# gameConsole.net
KiCad netlist of a schematic drawn in Altium Designer
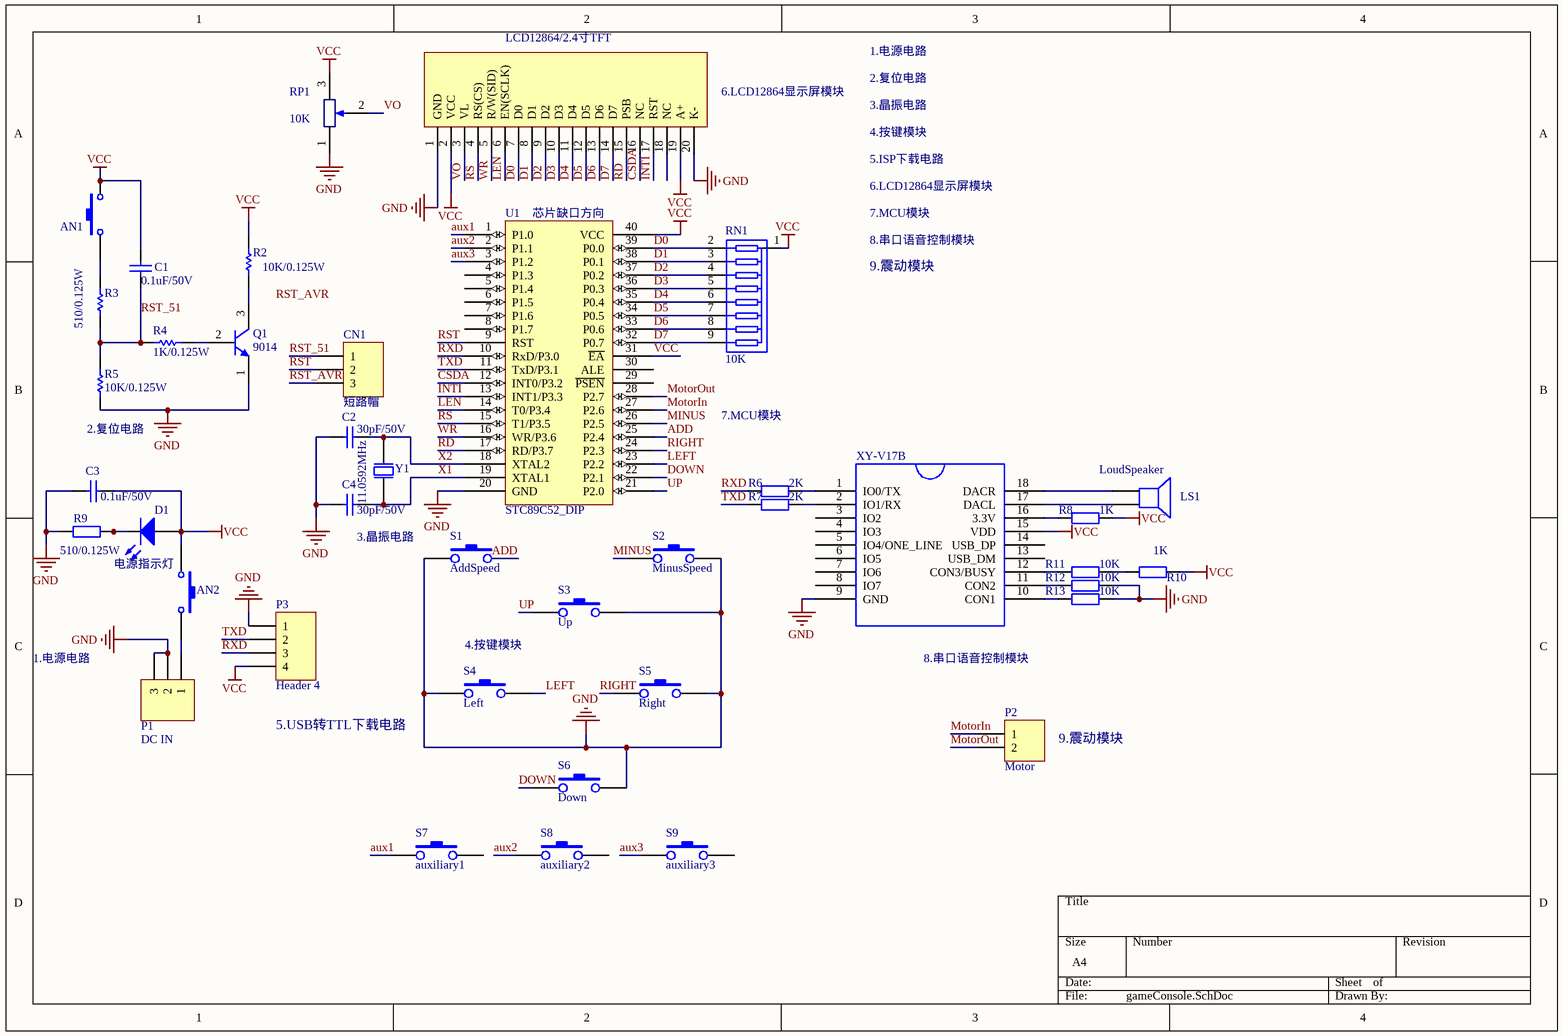
[diagram p0: gameConsole.SchDoc]

(export (version "E")
  (design (tool "Eeschema 10.0.6"))
  (components
    (comp (ref "AN1")
      (value "Button")
      (footprint "BUTTON_6*6")
      (fields (field (name "PUBLISHER") "Altium Limited"))
      (libsource (lib "03-EButterflyIntegratedLibrary") (part "Button"))
    )
    (comp (ref "AN2")
      (value "微动开关")
      (footprint "sw_8.5mm")
      (description "Button")
      (fields (field (name "PUBLISHER") "Altium Limited"))
      (libsource (lib "03-EButterflyIntegratedLibrary") (part "Button"))
    )
    (comp (ref "C1")
      (value "0.1uF/50V")
      (footprint "Cap")
      (description "Capacitor")
      (fields (field (name "PUBLISHER") "Altium Limited"))
      (libsource (lib "Miscellaneous Devices") (part "Cap"))
    )
    (comp (ref "C2")
      (value "30pF/50V")
      (footprint "Cap")
      (description "Capacitor")
      (fields (field (name "Comment") "Cap") (field (name "PUBLISHER") "Altium Limited"))
      (libsource (lib "Miscellaneous Devices") (part "Cap"))
    )
    (comp (ref "C3")
      (value "0.1uF/50V")
      (footprint "Cap")
      (description "Capacitor")
      (fields (field (name "PUBLISHER") "Altium Limited"))
      (libsource (lib "Miscellaneous Devices") (part "Cap"))
    )
    (comp (ref "C4")
      (value "30pF/50V")
      (footprint "Cap")
      (description "Capacitor")
      (fields (field (name "PUBLISHER") "Altium Limited"))
      (libsource (lib "Miscellaneous Devices") (part "Cap"))
    )
    (comp (ref "CN1")
      (value "短路帽")
      (footprint "SIP-3")
      (description "Header, 3-Pin")
      (fields (field (name "PUBLISHER") "Altium Limited"))
      (libsource (lib "01 Connect_IntegratedLibrary") (part "Header 3"))
    )
    (comp (ref "D1")
      (value "电源指示灯")
      (footprint "LED-1")
      (description "Typical RED GaAs LED")
      (fields (field (name "PUBLISHER") "Altium Limited"))
      (libsource (lib "Miscellaneous Devices") (part "LED1"))
    )
    (comp (ref "LCD1")
      (value "LCD12864/2.4寸TFT")
      (footprint "HDR1X20")
      (description "LCD12864 带字库")
      (libsource (lib "02 Miscellaneous_Devices_ZSF_Library") (part "LCD12864_1"))
    )
    (comp (ref "LS1")
      (value "LoudSpeaker")
      (footprint "扬声器")
      (description "Loudspeaker")
      (fields (field (name "PUBLISHER") "Altium Limited"))
      (libsource (lib "Miscellaneous Devices") (part "Speaker"))
    )
    (comp (ref "P1")
      (value "DC IN")
      (footprint "DC_IN")
      (description "Header, 3-Pin")
      (fields (field (name "PUBLISHER") "Altium Limited"))
      (libsource (lib "Miscellaneous Connectors") (part "Header 3"))
    )
    (comp (ref "P2")
      (value "Motor")
      (footprint "震动马达")
      (description "Header, 2-Pin")
      (fields (field (name "PUBLISHER") "Altium Limited"))
      (libsource (lib "Miscellaneous Connectors") (part "Header 2"))
    )
    (comp (ref "P3")
      (value "Header 4")
      (footprint "USB转TTL")
      (description "Header, 4-Pin")
      (fields (field (name "PUBLISHER") "Altium Limited"))
      (libsource (lib "01 Connect_IntegratedLibrary") (part "Header 4"))
    )
    (comp (ref "Q1")
      (value "9014")
      (footprint "TO-92-3L")
      (description "NPN型小功率三极管")
      (libsource (lib "02 Miscellaneous_Devices_ZSF_Library") (part "9014_TO-92"))
    )
    (comp (ref "R2")
      (value "10K/0.125W")
      (footprint "AXIAL-0.4")
      (description "Resistor")
      (fields (field (name "Comment") "Res1") (field (name "PUBLISHER") "Altium Limited"))
      (libsource (lib "Miscellaneous Devices") (part "Res1"))
    )
    (comp (ref "R3")
      (value "510/0.125W")
      (footprint "AXIAL-0.4")
      (description "Resistor")
      (fields (field (name "PUBLISHER") "Altium Limited"))
      (libsource (lib "Miscellaneous Devices") (part "Res1"))
    )
    (comp (ref "R4")
      (value "1K/0.125W")
      (footprint "AXIAL-0.4")
      (description "Resistor")
      (fields (field (name "PUBLISHER") "Altium Limited"))
      (libsource (lib "Miscellaneous Devices") (part "Res1"))
    )
    (comp (ref "R5")
      (value "10K/0.125W")
      (footprint "AXIAL-0.4")
      (description "Resistor")
      (fields (field (name "PUBLISHER") "Altium Limited"))
      (libsource (lib "Miscellaneous Devices") (part "Res1"))
    )
    (comp (ref "R6")
      (value "2K")
      (footprint "AXIAL-0.4")
      (description "Resistor")
      (fields (field (name "PUBLISHER") "Altium Limited"))
      (libsource (lib "Miscellaneous Devices") (part "Res2"))
    )
    (comp (ref "R7")
      (value "2K")
      (footprint "AXIAL-0.4")
      (description "Resistor")
      (fields (field (name "PUBLISHER") "Altium Limited"))
      (libsource (lib "Miscellaneous Devices") (part "Res2"))
    )
    (comp (ref "R8")
      (value "1K")
      (footprint "AXIAL-0.4")
      (description "Resistor")
      (fields (field (name "Comment") "Res2") (field (name "PUBLISHER") "Altium Limited"))
      (libsource (lib "Miscellaneous Devices") (part "Res2"))
    )
    (comp (ref "R9")
      (value "510/0.125W")
      (footprint "AXIAL-0.4")
      (description "Resistor")
      (fields (field (name "PUBLISHER") "Altium Limited"))
      (libsource (lib "Miscellaneous Devices") (part "Res2"))
    )
    (comp (ref "R10")
      (value "1K")
      (footprint "AXIAL-0.4")
      (description "Resistor")
      (fields (field (name "PUBLISHER") "Altium Limited"))
      (libsource (lib "Miscellaneous Devices") (part "Res2"))
    )
    (comp (ref "R11")
      (value "10K")
      (footprint "AXIAL-0.4")
      (description "Resistor")
      (fields (field (name "PUBLISHER") "Altium Limited"))
      (libsource (lib "Miscellaneous Devices") (part "Res2"))
    )
    (comp (ref "R12")
      (value "10K")
      (footprint "AXIAL-0.4")
      (description "Resistor")
      (fields (field (name "PUBLISHER") "Altium Limited"))
      (libsource (lib "Miscellaneous Devices") (part "Res2"))
    )
    (comp (ref "R13")
      (value "10K")
      (footprint "AXIAL-0.4")
      (description "Resistor")
      (fields (field (name "PUBLISHER") "Altium Limited"))
      (libsource (lib "Miscellaneous Devices") (part "Res2"))
    )
    (comp (ref "RN1")
      (value "10K")
      (footprint "RES-PACK-DIP9")
      (description "10K排阻")
      (fields (field (name "Comment") "Res Pack Single"))
      (libsource (lib "03-EButterflyIntegratedLibrary") (part "Res Pack Single"))
    )
    (comp (ref "RP1")
      (value "10K")
      (footprint "RP-3362")
      (description "WH148单联电位器 3脚 柄长15mm")
      (libsource (lib "02 Miscellaneous_Devices_ZSF_Library") (part "RP_WH148_Signal"))
    )
    (comp (ref "S1") (value "AddSpeed") (footprint "BUTTON_6*6") (libsource (lib "开关") (part "微动开关")))
    (comp (ref "S2") (value "MinusSpeed") (footprint "BUTTON_6*6") (libsource (lib "开关") (part "微动开关")))
    (comp (ref "S3") (value "Up") (footprint "BUTTON_6*6") (libsource (lib "开关") (part "微动开关")))
    (comp (ref "S4") (value "Left") (footprint "BUTTON_6*6") (libsource (lib "开关") (part "微动开关")))
    (comp (ref "S5") (value "Right") (footprint "BUTTON_6*6") (libsource (lib "开关") (part "微动开关")))
    (comp (ref "S6") (value "Down") (footprint "BUTTON_6*6") (libsource (lib "开关") (part "微动开关")))
    (comp (ref "S7") (value "auxiliary1") (footprint "BUTTON_6*6") (libsource (lib "开关") (part "微动开关")))
    (comp (ref "S8") (value "auxiliary2") (footprint "BUTTON_6*6") (libsource (lib "开关") (part "微动开关")))
    (comp (ref "S9") (value "auxiliary3") (footprint "BUTTON_6*6") (libsource (lib "开关") (part "微动开关")))
    (comp (ref "U1")
      (value "STC89C52_DIP")
      (footprint "DIP-40")
      (libsource (lib "02 Miscellaneous_Devices_ZSF_Library") (part "STC89C52_DIP"))
    )
    (comp (ref "XY-V17B") (value "XY-V17B") (footprint "SV1700A") (libsource (lib "Schlib1") (part "MODULE")))
    (comp (ref "Y1")
      (value "XTAL")
      (footprint "XTAL-49/U_N")
      (description "Crystal Oscillator")
      (fields (field (name "FREQUENCY") "11.0592MHz") (field (name "PUBLISHER") "Altium Limited"))
      (libsource (lib "03-EButterflyIntegratedLibrary") (part "XTAL"))
    )
  )
  (nets
    (net (code "1") (name "/ADD") (class "Default")
      (node (ref "S1") (pin "2") (pinfunction "2_2") (pintype "passive"))
      (node (ref "U1") (pin "25") (pinfunction "P2.4_25") (pintype "bidirectional"))
    )
    (net (code "2") (name "/CSDA") (class "Default")
      (node (ref "LCD1") (pin "16") (pinfunction "NC_16") (pintype "passive"))
      (node (ref "U1") (pin "12") (pinfunction "INT0/P3.2_12") (pintype "bidirectional"))
    )
    (net (code "3") (name "/D0") (class "Default")
      (node (ref "LCD1") (pin "7") (pinfunction "D0_7") (pintype "passive"))
      (node (ref "RN1") (pin "2") (pinfunction "2_2") (pintype "passive"))
      (node (ref "U1") (pin "39") (pinfunction "P0.0_39") (pintype "bidirectional"))
    )
    (net (code "4") (name "/D1") (class "Default")
      (node (ref "LCD1") (pin "8") (pinfunction "D1_8") (pintype "passive"))
      (node (ref "RN1") (pin "3") (pinfunction "3_3") (pintype "passive"))
      (node (ref "U1") (pin "38") (pinfunction "P0.1_38") (pintype "bidirectional"))
    )
    (net (code "5") (name "/D2") (class "Default")
      (node (ref "LCD1") (pin "9") (pinfunction "D2_9") (pintype "passive"))
      (node (ref "RN1") (pin "4") (pinfunction "4_4") (pintype "passive"))
      (node (ref "U1") (pin "37") (pinfunction "P0.2_37") (pintype "bidirectional"))
    )
    (net (code "6") (name "/D3") (class "Default")
      (node (ref "LCD1") (pin "10") (pinfunction "D3_10") (pintype "passive"))
      (node (ref "RN1") (pin "5") (pinfunction "5_5") (pintype "passive"))
      (node (ref "U1") (pin "36") (pinfunction "P0.3_36") (pintype "bidirectional"))
    )
    (net (code "7") (name "/D4") (class "Default")
      (node (ref "LCD1") (pin "11") (pinfunction "D4_11") (pintype "passive"))
      (node (ref "RN1") (pin "6") (pinfunction "6_6") (pintype "passive"))
      (node (ref "U1") (pin "35") (pinfunction "P0.4_35") (pintype "bidirectional"))
    )
    (net (code "8") (name "/D5") (class "Default")
      (node (ref "LCD1") (pin "12") (pinfunction "D5_12") (pintype "passive"))
      (node (ref "RN1") (pin "7") (pinfunction "7_7") (pintype "passive"))
      (node (ref "U1") (pin "34") (pinfunction "P0.5_34") (pintype "bidirectional"))
    )
    (net (code "9") (name "/D6") (class "Default")
      (node (ref "LCD1") (pin "13") (pinfunction "D6_13") (pintype "passive"))
      (node (ref "RN1") (pin "8") (pinfunction "8_8") (pintype "passive"))
      (node (ref "U1") (pin "33") (pinfunction "P0.6_33") (pintype "bidirectional"))
    )
    (net (code "10") (name "/D7") (class "Default")
      (node (ref "LCD1") (pin "14") (pinfunction "D7_14") (pintype "passive"))
      (node (ref "RN1") (pin "9") (pinfunction "9_9") (pintype "passive"))
      (node (ref "U1") (pin "32") (pinfunction "P0.7_32") (pintype "bidirectional"))
    )
    (net (code "11") (name "/DOWN") (class "Default")
      (node (ref "S6") (pin "1") (pinfunction "1_1") (pintype "passive"))
      (node (ref "U1") (pin "22") (pinfunction "P2.1_22") (pintype "bidirectional"))
    )
    (net (code "12") (name "/INTI") (class "Default")
      (node (ref "LCD1") (pin "17") (pinfunction "RST_17") (pintype "passive"))
      (node (ref "U1") (pin "13") (pinfunction "INT1/P3.3_13") (pintype "bidirectional"))
    )
    (net (code "13") (name "/LEFT") (class "Default")
      (node (ref "S4") (pin "2") (pinfunction "2_2") (pintype "passive"))
      (node (ref "U1") (pin "23") (pinfunction "P2.2_23") (pintype "bidirectional"))
    )
    (net (code "14") (name "/LEN") (class "Default")
      (node (ref "LCD1") (pin "6") (pinfunction "EN(SCLK)_6") (pintype "passive"))
      (node (ref "U1") (pin "14") (pinfunction "T0/P3.4_14") (pintype "bidirectional"))
    )
    (net (code "15") (name "/MINUS") (class "Default")
      (node (ref "S2") (pin "1") (pinfunction "1_1") (pintype "passive"))
      (node (ref "U1") (pin "26") (pinfunction "P2.5_26") (pintype "bidirectional"))
    )
    (net (code "16") (name "/MotorIn") (class "Default")
      (node (ref "P2") (pin "1") (pinfunction "1_1") (pintype "passive"))
      (node (ref "U1") (pin "27") (pinfunction "P2.6_27") (pintype "bidirectional"))
    )
    (net (code "17") (name "/MotorOut") (class "Default")
      (node (ref "P2") (pin "2") (pinfunction "2_2") (pintype "passive"))
      (node (ref "U1") (pin "28") (pinfunction "P2.7_28") (pintype "bidirectional"))
    )
    (net (code "18") (name "/RD") (class "Default")
      (node (ref "LCD1") (pin "15") (pinfunction "PSB_15") (pintype "passive"))
      (node (ref "U1") (pin "17") (pinfunction "RD/P3.7_17") (pintype "bidirectional"))
    )
    (net (code "19") (name "/RIGHT") (class "Default")
      (node (ref "S5") (pin "1") (pinfunction "1_1") (pintype "passive"))
      (node (ref "U1") (pin "24") (pinfunction "P2.3_24") (pintype "bidirectional"))
    )
    (net (code "20") (name "/RS") (class "Default")
      (node (ref "LCD1") (pin "4") (pinfunction "RS(CS)_4") (pintype "passive"))
      (node (ref "U1") (pin "15") (pinfunction "T1/P3.5_15") (pintype "bidirectional"))
    )
    (net (code "21") (name "/RST") (class "Default")
      (node (ref "CN1") (pin "2") (pinfunction "2_2") (pintype "passive"))
      (node (ref "U1") (pin "9") (pinfunction "RST_9") (pintype "passive"))
    )
    (net (code "22") (name "/RST_51") (class "Default")
      (node (ref "C1") (pin "1") (pinfunction "1_1") (pintype "passive"))
      (node (ref "CN1") (pin "1") (pinfunction "1_1") (pintype "passive"))
      (node (ref "R3") (pin "1") (pinfunction "1_1") (pintype "passive"))
      (node (ref "R4") (pin "2") (pinfunction "2_2") (pintype "passive"))
      (node (ref "R5") (pin "2") (pinfunction "2_2") (pintype "passive"))
    )
    (net (code "23") (name "/RST_AVR") (class "Default")
      (node (ref "CN1") (pin "3") (pinfunction "3_3") (pintype "passive"))
    )
    (net (code "24") (name "/RXD") (class "Default")
      (node (ref "P3") (pin "3") (pinfunction "3_3") (pintype "passive"))
      (node (ref "R6") (pin "1") (pinfunction "1_1") (pintype "passive"))
      (node (ref "U1") (pin "10") (pinfunction "RxD/P3.0_10") (pintype "bidirectional"))
    )
    (net (code "25") (name "/TXD") (class "Default")
      (node (ref "P3") (pin "2") (pinfunction "2_2") (pintype "passive"))
      (node (ref "R7") (pin "1") (pinfunction "1_1") (pintype "passive"))
      (node (ref "U1") (pin "11") (pinfunction "TxD/P3.1_11") (pintype "bidirectional"))
    )
    (net (code "26") (name "/UP") (class "Default")
      (node (ref "S3") (pin "1") (pinfunction "1_1") (pintype "passive"))
      (node (ref "U1") (pin "21") (pinfunction "P2.0_21") (pintype "bidirectional"))
    )
    (net (code "27") (name "/VO") (class "Default")
      (node (ref "LCD1") (pin "3") (pinfunction "VL_3") (pintype "passive"))
      (node (ref "RP1") (pin "2") (pinfunction "2_2") (pintype "passive"))
    )
    (net (code "28") (name "/WR") (class "Default")
      (node (ref "LCD1") (pin "5") (pinfunction "R/W(SID)_5") (pintype "passive"))
      (node (ref "U1") (pin "16") (pinfunction "WR/P3.6_16") (pintype "bidirectional"))
    )
    (net (code "29") (name "/X1") (class "Default")
      (node (ref "C4") (pin "1") (pinfunction "1_1") (pintype "passive"))
      (node (ref "U1") (pin "19") (pinfunction "XTAL1_19") (pintype "passive"))
      (node (ref "Y1") (pin "1") (pinfunction "OSC1_1") (pintype "passive"))
    )
    (net (code "30") (name "/X2") (class "Default")
      (node (ref "C2") (pin "1") (pinfunction "1_1") (pintype "passive"))
      (node (ref "U1") (pin "18") (pinfunction "XTAL2_18") (pintype "passive"))
      (node (ref "Y1") (pin "2") (pinfunction "OSC2_2") (pintype "passive"))
    )
    (net (code "31") (name "/aux1") (class "Default")
      (node (ref "S7") (pin "1") (pinfunction "1_1") (pintype "passive"))
      (node (ref "U1") (pin "1") (pinfunction "P1.0_1") (pintype "bidirectional"))
    )
    (net (code "32") (name "/aux2") (class "Default")
      (node (ref "S8") (pin "1") (pinfunction "1_1") (pintype "passive"))
      (node (ref "U1") (pin "2") (pinfunction "P1.1_2") (pintype "bidirectional"))
    )
    (net (code "33") (name "/aux3") (class "Default")
      (node (ref "S9") (pin "1") (pinfunction "1_1") (pintype "passive"))
      (node (ref "U1") (pin "3") (pinfunction "P1.2_3") (pintype "bidirectional"))
    )
    (net (code "34") (name "GND") (class "Default")
      (node (ref "C2") (pin "2") (pinfunction "2_2") (pintype "passive"))
      (node (ref "C3") (pin "1") (pinfunction "1_1") (pintype "passive"))
      (node (ref "C4") (pin "2") (pinfunction "2_2") (pintype "passive"))
      (node (ref "LCD1") (pin "1") (pinfunction "GND_1") (pintype "passive"))
      (node (ref "LCD1") (pin "20") (pinfunction "K-_20") (pintype "passive"))
      (node (ref "P1") (pin "2") (pinfunction "2_2") (pintype "passive"))
      (node (ref "P1") (pin "3") (pinfunction "3_3") (pintype "passive"))
      (node (ref "P3") (pin "1") (pinfunction "1_1") (pintype "passive"))
      (node (ref "Q1") (pin "1") (pinfunction "E_1") (pintype "passive"))
      (node (ref "R12") (pin "2") (pinfunction "2_2") (pintype "passive"))
      (node (ref "R13") (pin "2") (pinfunction "2_2") (pintype "passive"))
      (node (ref "R5") (pin "1") (pinfunction "1_1") (pintype "passive"))
      (node (ref "R9") (pin "1") (pinfunction "1_1") (pintype "passive"))
      (node (ref "RP1") (pin "1") (pinfunction "1_1") (pintype "passive"))
      (node (ref "S1") (pin "1") (pinfunction "1_1") (pintype "passive"))
      (node (ref "S2") (pin "2") (pinfunction "2_2") (pintype "passive"))
      (node (ref "S3") (pin "2") (pinfunction "2_2") (pintype "passive"))
      (node (ref "S4") (pin "1") (pinfunction "1_1") (pintype "passive"))
      (node (ref "S5") (pin "2") (pinfunction "2_2") (pintype "passive"))
      (node (ref "S6") (pin "2") (pinfunction "2_2") (pintype "passive"))
      (node (ref "U1") (pin "20") (pinfunction "GND_20") (pintype "power_in"))
      (node (ref "XY-V17B") (pin "9") (pinfunction "GND_9") (pintype "passive"))
    )
    (net (code "35") (name "Net-(AN1-Pad2)") (class "Default")
      (node (ref "AN1") (pin "2") (pinfunction "2_2") (pintype "passive"))
      (node (ref "R3") (pin "2") (pinfunction "2_2") (pintype "passive"))
    )
    (net (code "36") (name "Net-(AN2-Pad1)") (class "Default")
      (node (ref "AN2") (pin "1") (pinfunction "1_1") (pintype "passive"))
      (node (ref "P1") (pin "1") (pinfunction "1_1") (pintype "passive"))
    )
    (net (code "37") (name "Net-(D1-K)") (class "Default")
      (node (ref "D1") (pin "2") (pinfunction "K_2") (pintype "passive"))
      (node (ref "R9") (pin "2") (pinfunction "2_2") (pintype "passive"))
    )
    (net (code "38") (name "Net-(Q1-B)") (class "Default")
      (node (ref "Q1") (pin "2") (pinfunction "B_2") (pintype "passive"))
      (node (ref "R4") (pin "1") (pinfunction "1_1") (pintype "passive"))
    )
    (net (code "39") (name "Net-(Q1-C)") (class "Default")
      (node (ref "Q1") (pin "3") (pinfunction "C_3") (pintype "passive"))
      (node (ref "R2") (pin "2") (pinfunction "2_2") (pintype "passive"))
    )
    (net (code "40") (name "Net-(R10-Pad1)") (class "Default")
      (node (ref "R10") (pin "1") (pinfunction "1_1") (pintype "passive"))
      (node (ref "R11") (pin "2") (pinfunction "2_2") (pintype "passive"))
    )
    (net (code "41") (name "Net-(XY-V17B-3.3V)") (class "Default")
      (node (ref "R8") (pin "1") (pinfunction "1_1") (pintype "passive"))
      (node (ref "XY-V17B") (pin "16") (pinfunction "3.3V_16") (pintype "passive"))
    )
    (net (code "42") (name "Net-(XY-V17B-CON1)") (class "Default")
      (node (ref "R13") (pin "1") (pinfunction "1_1") (pintype "passive"))
      (node (ref "XY-V17B") (pin "10") (pinfunction "CON1_10") (pintype "passive"))
    )
    (net (code "43") (name "Net-(XY-V17B-CON2)") (class "Default")
      (node (ref "R12") (pin "1") (pinfunction "1_1") (pintype "passive"))
      (node (ref "XY-V17B") (pin "11") (pinfunction "CON2_11") (pintype "passive"))
    )
    (net (code "44") (name "Net-(XY-V17B-CON3{slash}BUSY)") (class "Default")
      (node (ref "R11") (pin "1") (pinfunction "1_1") (pintype "passive"))
      (node (ref "XY-V17B") (pin "12") (pinfunction "CON3/BUSY_12") (pintype "passive"))
    )
    (net (code "45") (name "Net-(XY-V17B-DACL)") (class "Default")
      (node (ref "LS1") (pin "2") (pinfunction "2_2") (pintype "passive"))
      (node (ref "XY-V17B") (pin "17") (pinfunction "DACL_17") (pintype "passive"))
    )
    (net (code "46") (name "Net-(XY-V17B-DACR)") (class "Default")
      (node (ref "LS1") (pin "1") (pinfunction "1_1") (pintype "passive"))
      (node (ref "XY-V17B") (pin "18") (pinfunction "DACR_18") (pintype "passive"))
    )
    (net (code "47") (name "Net-(XY-V17B-IO0{slash}TX)") (class "Default")
      (node (ref "R6") (pin "2") (pinfunction "2_2") (pintype "passive"))
      (node (ref "XY-V17B") (pin "1") (pinfunction "IO0/TX_1") (pintype "passive"))
    )
    (net (code "48") (name "Net-(XY-V17B-IO1{slash}RX)") (class "Default")
      (node (ref "R7") (pin "2") (pinfunction "2_2") (pintype "passive"))
      (node (ref "XY-V17B") (pin "2") (pinfunction "IO1/RX_2") (pintype "passive"))
    )
    (net (code "49") (name "VCC") (class "Default")
      (node (ref "AN1") (pin "1") (pinfunction "1_1") (pintype "passive"))
      (node (ref "AN2") (pin "2") (pinfunction "2_2") (pintype "passive"))
      (node (ref "C1") (pin "2") (pinfunction "2_2") (pintype "passive"))
      (node (ref "C3") (pin "2") (pinfunction "2_2") (pintype "passive"))
      (node (ref "D1") (pin "1") (pinfunction "A_1") (pintype "passive"))
      (node (ref "LCD1") (pin "19") (pinfunction "A+_19") (pintype "passive"))
      (node (ref "LCD1") (pin "2") (pinfunction "VCC_2") (pintype "passive"))
      (node (ref "P3") (pin "4") (pinfunction "4_4") (pintype "passive"))
      (node (ref "R10") (pin "2") (pinfunction "2_2") (pintype "passive"))
      (node (ref "R2") (pin "1") (pinfunction "1_1") (pintype "passive"))
      (node (ref "R8") (pin "2") (pinfunction "2_2") (pintype "passive"))
      (node (ref "RN1") (pin "1") (pinfunction "1_1") (pintype "passive"))
      (node (ref "RP1") (pin "3") (pinfunction "3_3") (pintype "passive"))
      (node (ref "U1") (pin "31") (pinfunction "~{EA}_31") (pintype "passive"))
      (node (ref "U1") (pin "40") (pinfunction "VCC_40") (pintype "power_in"))
      (node (ref "XY-V17B") (pin "15") (pinfunction "VDD_15") (pintype "passive"))
    )
    (net (code "50") (name "unconnected-(LCD1-NC-Pad18)") (class "Default")
      (node (ref "LCD1") (pin "18") (pinfunction "NC_18") (pintype "passive"))
    )
    (net (code "51") (name "unconnected-(S7-Pad2)") (class "Default")
      (node (ref "S7") (pin "2") (pinfunction "2_2") (pintype "passive"))
    )
    (net (code "52") (name "unconnected-(S8-Pad2)") (class "Default")
      (node (ref "S8") (pin "2") (pinfunction "2_2") (pintype "passive"))
    )
    (net (code "53") (name "unconnected-(S9-Pad2)") (class "Default")
      (node (ref "S9") (pin "2") (pinfunction "2_2") (pintype "passive"))
    )
    (net (code "54") (name "unconnected-(U1-ALE-Pad30)") (class "Default")
      (node (ref "U1") (pin "30") (pinfunction "ALE_30") (pintype "passive"))
    )
    (net (code "55") (name "unconnected-(U1-P1.3-Pad4)") (class "Default")
      (node (ref "U1") (pin "4") (pinfunction "P1.3_4") (pintype "bidirectional"))
    )
    (net (code "56") (name "unconnected-(U1-P1.4-Pad5)") (class "Default")
      (node (ref "U1") (pin "5") (pinfunction "P1.4_5") (pintype "bidirectional"))
    )
    (net (code "57") (name "unconnected-(U1-P1.5-Pad6)") (class "Default")
      (node (ref "U1") (pin "6") (pinfunction "P1.5_6") (pintype "bidirectional"))
    )
    (net (code "58") (name "unconnected-(U1-P1.6-Pad7)") (class "Default")
      (node (ref "U1") (pin "7") (pinfunction "P1.6_7") (pintype "bidirectional"))
    )
    (net (code "59") (name "unconnected-(U1-P1.7-Pad8)") (class "Default")
      (node (ref "U1") (pin "8") (pinfunction "P1.7_8") (pintype "bidirectional"))
    )
    (net (code "60") (name "unconnected-(U1-~{PSEN}-Pad29)") (class "Default")
      (node (ref "U1") (pin "29") (pinfunction "~{PSEN}_29") (pintype "passive"))
    )
    (net (code "61") (name "unconnected-(XY-V17B-IO2-Pad3)") (class "Default")
      (node (ref "XY-V17B") (pin "3") (pinfunction "IO2_3") (pintype "passive"))
    )
    (net (code "62") (name "unconnected-(XY-V17B-IO3-Pad4)") (class "Default")
      (node (ref "XY-V17B") (pin "4") (pinfunction "IO3_4") (pintype "passive"))
    )
    (net (code "63") (name "unconnected-(XY-V17B-IO4{slash}ONE_LINE-Pad5)") (class "Default")
      (node (ref "XY-V17B") (pin "5") (pinfunction "IO4/ONE_LINE_5") (pintype "passive"))
    )
    (net (code "64") (name "unconnected-(XY-V17B-IO5-Pad6)") (class "Default")
      (node (ref "XY-V17B") (pin "6") (pinfunction "IO5_6") (pintype "passive"))
    )
    (net (code "65") (name "unconnected-(XY-V17B-IO6-Pad7)") (class "Default")
      (node (ref "XY-V17B") (pin "7") (pinfunction "IO6_7") (pintype "passive"))
    )
    (net (code "66") (name "unconnected-(XY-V17B-IO7-Pad8)") (class "Default")
      (node (ref "XY-V17B") (pin "8") (pinfunction "IO7_8") (pintype "passive"))
    )
    (net (code "67") (name "unconnected-(XY-V17B-USB_DM-Pad13)") (class "Default")
      (node (ref "XY-V17B") (pin "13") (pinfunction "USB_DM_13") (pintype "passive"))
    )
    (net (code "68") (name "unconnected-(XY-V17B-USB_DP-Pad14)") (class "Default")
      (node (ref "XY-V17B") (pin "14") (pinfunction "USB_DP_14") (pintype "passive"))
    )
  )
)
